# CAN2XG_TCAN.net
KiCad netlist of a schematic drawn in Altium Designer
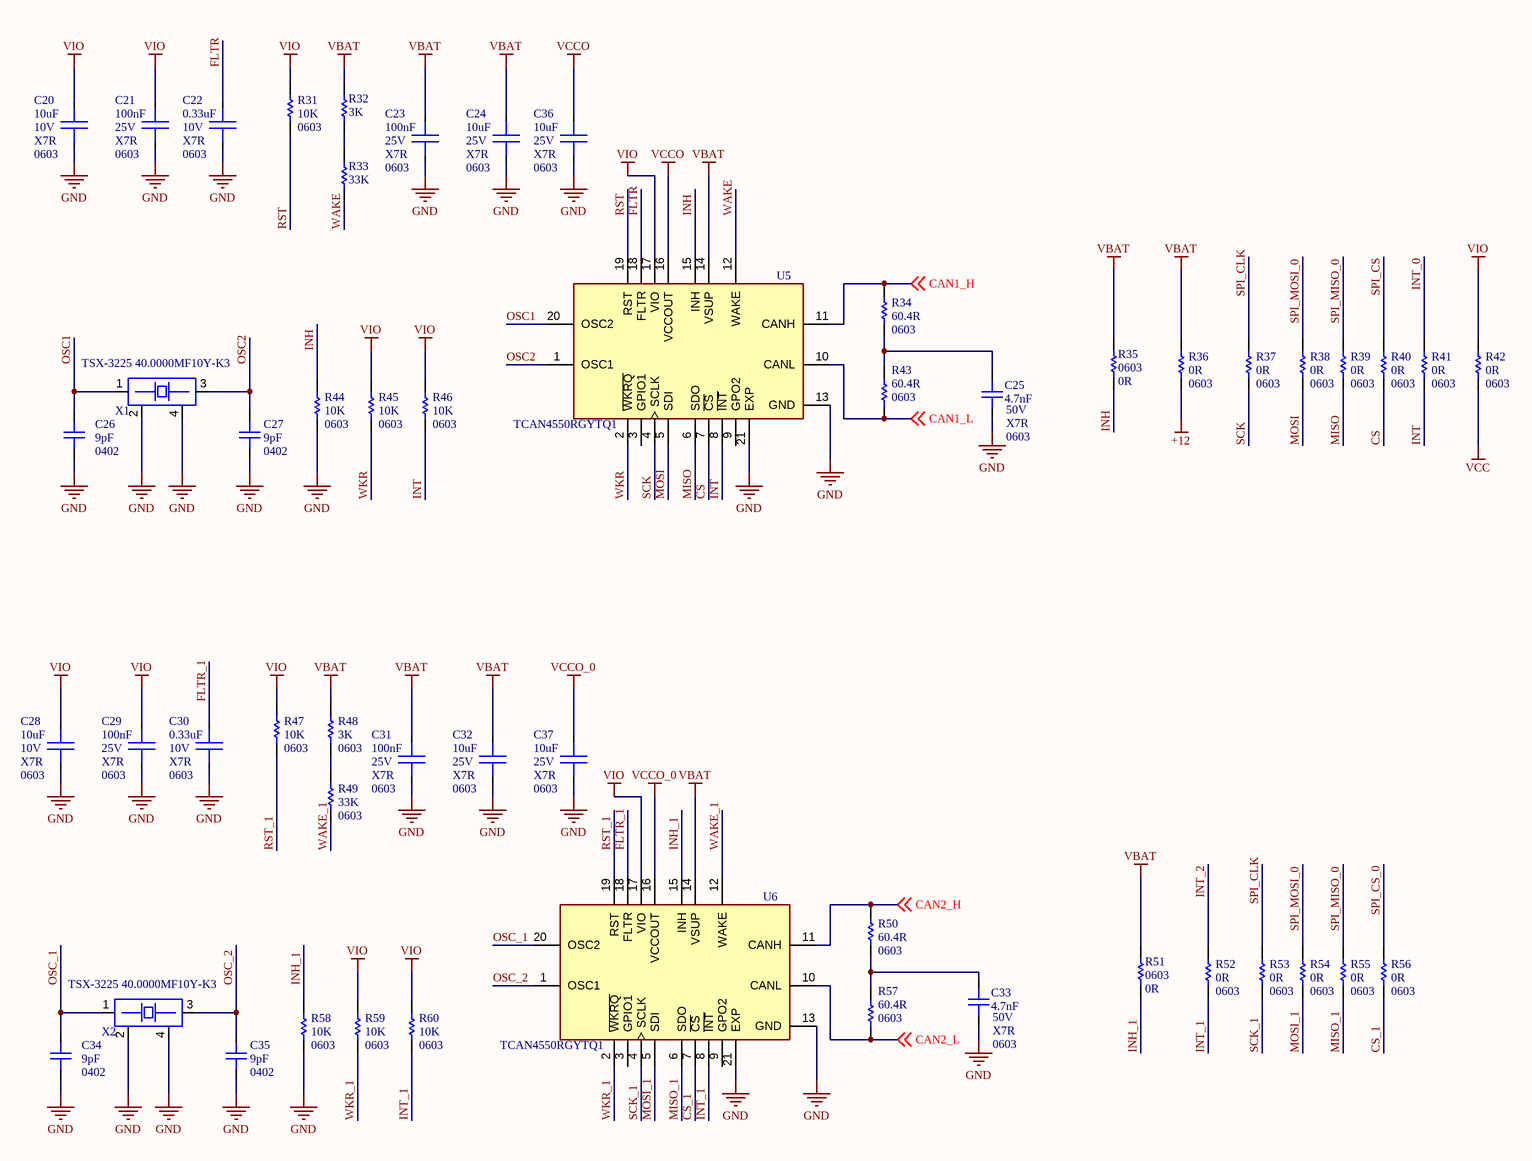
[diagram p0: CAN2XG_TCAN.SchDoc]

(export (version "E")
  (design (tool "Eeschema 10.0.6"))
  (components
    (comp (ref "C20")
      (value "10uF")
      (footprint "CAP-0603")
      (description "CAP CER 10uF 25V  0603")
      (fields
        (field (name "VOLTAGE") "10V")
        (field (name "DIELECTIRC") "X7R")
        (field (name "CASE/PACKAGE") "0603")
      )
      (libsource (lib "CAN2ET") (part "C10uF  0603"))
    )
    (comp (ref "C21")
      (value "100nF")
      (footprint "CAP-0603")
      (description "CAP CER 100nF 25V X7R 0603")
      (fields
        (field (name "VOLTAGE") "25V")
        (field (name "DIELECTIRC") "X7R")
        (field (name "CASE/PACKAGE") "0603")
      )
      (libsource (lib "CAN2ET") (part "C10uF  0603"))
    )
    (comp (ref "C22")
      (value "0.33uF")
      (footprint "CAP-0603")
      (description "CAP CER 0.33uF 10V  0603")
      (fields
        (field (name "VOLTAGE") "10V")
        (field (name "DIELECTIRC") "X7R")
        (field (name "CASE/PACKAGE") "0603")
      )
      (libsource (lib "CAN2ET") (part "C10uF  0603"))
    )
    (comp (ref "C23")
      (value "100nF")
      (footprint "CAP-0603")
      (description "CAP CER 100nF 25V X7R 0603")
      (fields
        (field (name "VOLTAGE") "25V")
        (field (name "DIELECTIRC") "X7R")
        (field (name "CASE/PACKAGE") "0603")
      )
      (libsource (lib "CAN2ET") (part "C10uF  0603"))
    )
    (comp (ref "C24")
      (value "10uF")
      (footprint "CAP-0603")
      (description "CAP CER 10uF 25V  0603")
      (fields
        (field (name "VOLTAGE") "25V")
        (field (name "DIELECTIRC") "X7R")
        (field (name "CASE/PACKAGE") "0603")
      )
      (libsource (lib "CAN2ET") (part "C10uF  0603"))
    )
    (comp (ref "C25")
      (value "4.7nF")
      (footprint "CAP-0603")
      (description "CAP CER 4.7nF 50V X7R 0603")
      (fields
        (field (name "VOLTAGE") "50V")
        (field (name "DIELECTRIC") "X7R")
        (field (name "CASE/PACKAGE") "0603")
      )
      (libsource (lib "CN2XET") (part "CS0805KRX7RYBB472"))
    )
    (comp (ref "C26")
      (value "9pF")
      (footprint "CAPC0402")
      (description "CAP CER 9PF 50V X7R 0402")
      (fields (field (name "CASE/PACKAGE") "0402") (field (name "VOLTAGE") "50V"))
      (libsource (lib "CN2XET") (part "CQ0805BRNPOYBN8R2"))
    )
    (comp (ref "C27")
      (value "9pF")
      (footprint "CAPC0402")
      (description "CAP CER 9PF 50V X7R 0402")
      (fields (field (name "CASE/PACKAGE") "0402") (field (name "VOLTAGE") "50V"))
      (libsource (lib "CN2XET") (part "CQ0805BRNPOYBN8R2"))
    )
    (comp (ref "C28")
      (value "10uF")
      (footprint "CAP-0603")
      (description "CAP CER 10uF 25V  0603")
      (fields
        (field (name "VOLTAGE") "10V")
        (field (name "DIELECTIRC") "X7R")
        (field (name "CASE/PACKAGE") "0603")
      )
      (libsource (lib "CAN2ET") (part "C10uF  0603"))
    )
    (comp (ref "C29")
      (value "100nF")
      (footprint "CAP-0603")
      (description "CAP CER 100nF 25V X7R 0603")
      (fields
        (field (name "VOLTAGE") "25V")
        (field (name "DIELECTIRC") "X7R")
        (field (name "CASE/PACKAGE") "0603")
      )
      (libsource (lib "CAN2ET") (part "C10uF  0603"))
    )
    (comp (ref "C30")
      (value "0.33uF")
      (footprint "CAP-0603")
      (description "CAP CER 0.33uF 10V  0603")
      (fields
        (field (name "VOLTAGE") "10V")
        (field (name "DIELECTIRC") "X7R")
        (field (name "CASE/PACKAGE") "0603")
      )
      (libsource (lib "CAN2ET") (part "C10uF  0603"))
    )
    (comp (ref "C31")
      (value "100nF")
      (footprint "CAP-0603")
      (description "CAP CER 100nF 25V X7R 0603")
      (fields
        (field (name "VOLTAGE") "25V")
        (field (name "DIELECTIRC") "X7R")
        (field (name "CASE/PACKAGE") "0603")
      )
      (libsource (lib "CAN2ET") (part "C10uF  0603"))
    )
    (comp (ref "C32")
      (value "10uF")
      (footprint "CAP-0603")
      (description "CAP CER 10uF 25V  0603")
      (fields
        (field (name "VOLTAGE") "25V")
        (field (name "DIELECTIRC") "X7R")
        (field (name "CASE/PACKAGE") "0603")
      )
      (libsource (lib "CAN2ET") (part "C10uF  0603"))
    )
    (comp (ref "C33")
      (value "4.7nF")
      (footprint "CAP-0603")
      (description "CAP CER 4.7nF 50V X7R 0603")
      (fields
        (field (name "VOLTAGE") "50V")
        (field (name "DIELECTRIC") "X7R")
        (field (name "CASE/PACKAGE") "0603")
      )
      (libsource (lib "CN2XET") (part "CS0805KRX7RYBB472"))
    )
    (comp (ref "C34")
      (value "9pF")
      (footprint "CAPC0402")
      (description "CAP CER 9PF 50V X7R 0402")
      (fields (field (name "CASE/PACKAGE") "0402") (field (name "VOLTAGE") "50V"))
      (libsource (lib "CN2XET") (part "CQ0805BRNPOYBN8R2"))
    )
    (comp (ref "C35")
      (value "9pF")
      (footprint "CAPC0402")
      (description "CAP CER 9PF 50V X7R 0402")
      (fields (field (name "CASE/PACKAGE") "0402") (field (name "VOLTAGE") "50V"))
      (libsource (lib "CN2XET") (part "CQ0805BRNPOYBN8R2"))
    )
    (comp (ref "C36")
      (value "10uF")
      (footprint "CAP-0603")
      (description "CAP CER 10uF 25V  0603")
      (fields
        (field (name "VOLTAGE") "25V")
        (field (name "DIELECTIRC") "X7R")
        (field (name "CASE/PACKAGE") "0603")
      )
      (libsource (lib "CAN2ET") (part "C10uF  0603"))
    )
    (comp (ref "C37")
      (value "10uF")
      (footprint "CAP-0603")
      (description "CAP CER 10uF 25V  0603")
      (fields
        (field (name "VOLTAGE") "25V")
        (field (name "DIELECTIRC") "X7R")
        (field (name "CASE/PACKAGE") "0603")
      )
      (libsource (lib "CAN2ET") (part "C10uF  0603"))
    )
    (comp (ref "R31")
      (value "10K")
      (footprint "RESC0603")
      (description "Thick Film Resistor -  10K, 1%, 0603")
      (fields (field (name "CASE/PACKAGE") "0603"))
      (libsource (lib "CN2XET") (part "ERJ6ENF1002V"))
    )
    (comp (ref "R32")
      (value "3K")
      (footprint "RESC0603")
      (description "Thick Film Resistor -  3K, 1%, 0603")
      (libsource (lib "CN2XET") (part "ERJ6ENF1002V"))
    )
    (comp (ref "R33")
      (value "33K")
      (footprint "RESC0603")
      (description "Thick Film Resistor -  33K, 1%, 0603")
      (libsource (lib "CN2XET") (part "ERJ6ENF1002V"))
    )
    (comp (ref "R34")
      (value "60.4R")
      (footprint "RESC0603")
      (description "Thick Film Resistor -  60.4R, 1%, 0603")
      (fields (field (name "CASE/PACKAGE") "0603"))
      (libsource (lib "CN2XET") (part "RC0805FR-0760R4L"))
    )
    (comp (ref "R35")
      (value "0R")
      (footprint "RESC0603")
      (description "Thick Film Resistor -  0R , 1%, 0603")
      (fields (field (name "CASE/PACKAGE") "0603"))
      (libsource (lib "CN2XET") (part "RC0805FR-0760R4L"))
    )
    (comp (ref "R36")
      (value "0R")
      (footprint "RESC0603")
      (description "Thick Film Resistor -  0R , 1%, 0603")
      (fields (field (name "CASE/PACKAGE") "0603"))
      (libsource (lib "CN2XET") (part "RC0805FR-0760R4L"))
    )
    (comp (ref "R37")
      (value "0R")
      (footprint "RESC0603")
      (description "Thick Film Resistor -  0R , 1%, 0603")
      (fields (field (name "CASE/PACKAGE") "0603"))
      (libsource (lib "CN2XET") (part "RC0805FR-0760R4L"))
    )
    (comp (ref "R38")
      (value "0R")
      (footprint "RESC0603")
      (description "Thick Film Resistor -  0R , 1%, 0603")
      (fields (field (name "CASE/PACKAGE") "0603"))
      (libsource (lib "CN2XET") (part "RC0805FR-0760R4L"))
    )
    (comp (ref "R39")
      (value "0R")
      (footprint "RESC0603")
      (description "Thick Film Resistor -  0R , 1%, 0603")
      (fields (field (name "CASE/PACKAGE") "0603"))
      (libsource (lib "CN2XET") (part "RC0805FR-0760R4L"))
    )
    (comp (ref "R40")
      (value "0R")
      (footprint "RESC0603")
      (description "Thick Film Resistor -  0R , 1%, 0603")
      (fields (field (name "CASE/PACKAGE") "0603"))
      (libsource (lib "CN2XET") (part "RC0805FR-0760R4L"))
    )
    (comp (ref "R41")
      (value "0R")
      (footprint "RESC0603")
      (description "Thick Film Resistor -  0R , 1%, 0603")
      (fields (field (name "CASE/PACKAGE") "0603"))
      (libsource (lib "CN2XET") (part "RC0805FR-0760R4L"))
    )
    (comp (ref "R42")
      (value "0R")
      (footprint "RESC0603")
      (description "Thick Film Resistor -  0R , 1%, 0603")
      (fields (field (name "CASE/PACKAGE") "0603"))
      (libsource (lib "CN2XET") (part "RC0805FR-0760R4L"))
    )
    (comp (ref "R43")
      (value "60.4R")
      (footprint "RESC0603")
      (description "Thick Film Resistor -  60.4R, 1%, 0603")
      (fields (field (name "CASE/PACKAGE") "0603"))
      (libsource (lib "CN2XET") (part "RC0805FR-0760R4L"))
    )
    (comp (ref "R44")
      (value "10K")
      (footprint "RESC0603")
      (description "Thick Film Resistor -  10K, 1%, 0603")
      (fields (field (name "CASE/PACKAGE") "0603"))
      (libsource (lib "CN2XET") (part "ERJ6ENF1002V"))
    )
    (comp (ref "R45")
      (value "10K")
      (footprint "RESC0603")
      (description "Thick Film Resistor -  10K, 1%, 0603")
      (fields (field (name "CASE/PACKAGE") "0603"))
      (libsource (lib "CN2XET") (part "ERJ6ENF1002V"))
    )
    (comp (ref "R46")
      (value "10K")
      (footprint "RESC0603")
      (description "Thick Film Resistor -  10K, 1%, 0603")
      (fields (field (name "CASE/PACKAGE") "0603"))
      (libsource (lib "CN2XET") (part "ERJ6ENF1002V"))
    )
    (comp (ref "R47")
      (value "10K")
      (footprint "RESC0603")
      (description "Thick Film Resistor -  10K, 1%, 0603")
      (fields (field (name "CASE/PACKAGE") "0603"))
      (libsource (lib "CN2XET") (part "ERJ6ENF1002V"))
    )
    (comp (ref "R48")
      (value "3K")
      (footprint "RESC0603")
      (description "Thick Film Resistor -  3K, 1%, 0603")
      (fields (field (name "CASE/PACKAGE") "0603"))
      (libsource (lib "CN2XET") (part "ERJ6ENF1002V"))
    )
    (comp (ref "R49")
      (value "33K")
      (footprint "RESC0603")
      (description "Thick Film Resistor -  33K, 1%, 0603")
      (fields (field (name "CASE/PACKAGE") "0603"))
      (libsource (lib "CN2XET") (part "ERJ6ENF1002V"))
    )
    (comp (ref "R50")
      (value "60.4R")
      (footprint "RESC0603")
      (description "Thick Film Resistor -  60.4R, 1%, 0603")
      (fields (field (name "CASE/PACKAGE") "0603"))
      (libsource (lib "CN2XET") (part "RC0805FR-0760R4L"))
    )
    (comp (ref "R51")
      (value "0R")
      (footprint "RESC0603")
      (description "Thick Film Resistor -  0R , 1%, 0603")
      (fields (field (name "CASE/PACKAGE") "0603"))
      (libsource (lib "CN2XET") (part "RC0805FR-0760R4L"))
    )
    (comp (ref "R52")
      (value "0R")
      (footprint "RESC0603")
      (description "Thick Film Resistor -  0R , 1%, 0603")
      (fields (field (name "CASE/PACKAGE") "0603"))
      (libsource (lib "CN2XET") (part "RC0805FR-0760R4L"))
    )
    (comp (ref "R53")
      (value "0R")
      (footprint "RESC0603")
      (description "Thick Film Resistor -  0R , 1%, 0603")
      (fields (field (name "CASE/PACKAGE") "0603"))
      (libsource (lib "CN2XET") (part "RC0805FR-0760R4L"))
    )
    (comp (ref "R54")
      (value "0R")
      (footprint "RESC0603")
      (description "Thick Film Resistor -  0R , 1%, 0603")
      (fields (field (name "CASE/PACKAGE") "0603"))
      (libsource (lib "CN2XET") (part "RC0805FR-0760R4L"))
    )
    (comp (ref "R55")
      (value "0R")
      (footprint "RESC0603")
      (description "Thick Film Resistor -  0R , 1%, 0603")
      (fields (field (name "CASE/PACKAGE") "0603"))
      (libsource (lib "CN2XET") (part "RC0805FR-0760R4L"))
    )
    (comp (ref "R56")
      (value "0R")
      (footprint "RESC0603")
      (description "Thick Film Resistor -  0R , 1%, 0603")
      (fields (field (name "CASE/PACKAGE") "0603"))
      (libsource (lib "CN2XET") (part "RC0805FR-0760R4L"))
    )
    (comp (ref "R57")
      (value "60.4R")
      (footprint "RESC0603")
      (description "Thick Film Resistor -  60.4R, 1%, 0603")
      (fields (field (name "CASE/PACKAGE") "0603"))
      (libsource (lib "CN2XET") (part "RC0805FR-0760R4L"))
    )
    (comp (ref "R58")
      (value "10K")
      (footprint "RESC0603")
      (description "Thick Film Resistor -  10K, 1%, 0603")
      (fields (field (name "CASE/PACKAGE") "0603"))
      (libsource (lib "CN2XET") (part "ERJ6ENF1002V"))
    )
    (comp (ref "R59")
      (value "10K")
      (footprint "RESC0603")
      (description "Thick Film Resistor -  10K, 1%, 0603")
      (fields (field (name "CASE/PACKAGE") "0603"))
      (libsource (lib "CN2XET") (part "ERJ6ENF1002V"))
    )
    (comp (ref "R60")
      (value "10K")
      (footprint "RESC0603")
      (description "Thick Film Resistor -  10K, 1%, 0603")
      (fields (field (name "CASE/PACKAGE") "0603"))
      (libsource (lib "CN2XET") (part "ERJ6ENF1002V"))
    )
    (comp (ref "U5")
      (value "~")
      (footprint "IC_TCAN4550RGYTQ1")
      (fields (field (name "MANUFACTURER PART NUMBER") "TCAN4550RGYTQ1"))
      (libsource (lib "CAN2XG") (part "TCAN4550RGYTQ1"))
    )
    (comp (ref "U6")
      (value "~")
      (footprint "IC_TCAN4550RGYTQ1")
      (fields (field (name "MANUFACTURER PART NUMBER") "TCAN4550RGYTQ1"))
      (libsource (lib "CAN2XG") (part "TCAN4550RGYTQ1"))
    )
    (comp (ref "X1")
      (value "~")
      (footprint "Crystal_3225")
      (description "CRYSTAL 40.0000MHZ 10PF SMD")
      (fields (field (name "MANUFACTURER PART NUMBER") "TSX-3225 40.0000MF10Y-K3"))
      (libsource (lib "CAN2XG") (part "CRYSTAL_1"))
    )
    (comp (ref "X2")
      (value "~")
      (footprint "Crystal_3225")
      (description "CRYSTAL 40.0000MHZ 10PF SMD")
      (fields (field (name "MANUFACTURER PART NUMBER") "TSX-3225 40.0000MF10Y-K3"))
      (libsource (lib "CAN2XG") (part "CRYSTAL_1"))
    )
  )
  (nets
    (net (code "1") (name "+12") (class "Default")
      (node (ref "R36") (pin "1") (pinfunction "1_1") (pintype "passive"))
    )
    (net (code "2") (name "/CS") (class "Default")
      (node (ref "R40") (pin "1") (pinfunction "1_1") (pintype "passive"))
      (node (ref "U5") (pin "7") (pinfunction "~{CS}_7") (pintype "passive"))
    )
    (net (code "3") (name "/CS_1") (class "Default")
      (node (ref "R56") (pin "1") (pinfunction "1_1") (pintype "passive"))
      (node (ref "U6") (pin "7") (pinfunction "~{CS}_7") (pintype "passive"))
    )
    (net (code "4") (name "/FLTR") (class "Default")
      (node (ref "C22") (pin "2") (pinfunction "2_2") (pintype "passive"))
      (node (ref "U5") (pin "18") (pinfunction "FLTR_18") (pintype "passive"))
    )
    (net (code "5") (name "/FLTR_1") (class "Default")
      (node (ref "C30") (pin "2") (pinfunction "2_2") (pintype "passive"))
      (node (ref "U6") (pin "18") (pinfunction "FLTR_18") (pintype "passive"))
    )
    (net (code "6") (name "/INH") (class "Default")
      (node (ref "R35") (pin "2") (pinfunction "2_2") (pintype "passive"))
      (node (ref "R44") (pin "2") (pinfunction "2_2") (pintype "passive"))
      (node (ref "U5") (pin "15") (pinfunction "INH_15") (pintype "passive"))
    )
    (net (code "7") (name "/INH_1") (class "Default")
      (node (ref "R51") (pin "2") (pinfunction "2_2") (pintype "passive"))
      (node (ref "R58") (pin "2") (pinfunction "2_2") (pintype "passive"))
      (node (ref "U6") (pin "15") (pinfunction "INH_15") (pintype "passive"))
    )
    (net (code "8") (name "/INT") (class "Default")
      (node (ref "R41") (pin "1") (pinfunction "1_1") (pintype "passive"))
      (node (ref "R46") (pin "1") (pinfunction "1_1") (pintype "passive"))
      (node (ref "U5") (pin "8") (pinfunction "~{INT}_8") (pintype "passive"))
    )
    (net (code "9") (name "/INT_0") (class "Default")
      (node (ref "R41") (pin "2") (pinfunction "2_2") (pintype "passive"))
    )
    (net (code "10") (name "/INT_1") (class "Default")
      (node (ref "R52") (pin "1") (pinfunction "1_1") (pintype "passive"))
      (node (ref "R60") (pin "1") (pinfunction "1_1") (pintype "passive"))
      (node (ref "U6") (pin "8") (pinfunction "~{INT}_8") (pintype "passive"))
    )
    (net (code "11") (name "/INT_2") (class "Default")
      (node (ref "R52") (pin "2") (pinfunction "2_2") (pintype "passive"))
    )
    (net (code "12") (name "/MISO") (class "Default")
      (node (ref "R39") (pin "1") (pinfunction "1_1") (pintype "passive"))
      (node (ref "U5") (pin "6") (pinfunction "SDO_6") (pintype "passive"))
    )
    (net (code "13") (name "/MISO_1") (class "Default")
      (node (ref "R55") (pin "1") (pinfunction "1_1") (pintype "passive"))
      (node (ref "U6") (pin "6") (pinfunction "SDO_6") (pintype "passive"))
    )
    (net (code "14") (name "/MOSI") (class "Default")
      (node (ref "R38") (pin "1") (pinfunction "1_1") (pintype "passive"))
      (node (ref "U5") (pin "5") (pinfunction "SDI_5") (pintype "passive"))
    )
    (net (code "15") (name "/MOSI_1") (class "Default")
      (node (ref "R54") (pin "1") (pinfunction "1_1") (pintype "passive"))
      (node (ref "U6") (pin "5") (pinfunction "SDI_5") (pintype "passive"))
    )
    (net (code "16") (name "/OSC1") (class "Default")
      (node (ref "C26") (pin "2") (pinfunction "2_2") (pintype "passive"))
      (node (ref "U5") (pin "20") (pinfunction "OSC2_20") (pintype "passive"))
      (node (ref "X1") (pin "1") (pinfunction "1_1") (pintype "passive"))
    )
    (net (code "17") (name "/OSC2") (class "Default")
      (node (ref "C27") (pin "2") (pinfunction "2_2") (pintype "passive"))
      (node (ref "U5") (pin "1") (pinfunction "OSC1_1") (pintype "passive"))
      (node (ref "X1") (pin "3") (pinfunction "3_3") (pintype "passive"))
    )
    (net (code "18") (name "/OSC_1") (class "Default")
      (node (ref "C34") (pin "2") (pinfunction "2_2") (pintype "passive"))
      (node (ref "U6") (pin "20") (pinfunction "OSC2_20") (pintype "passive"))
      (node (ref "X2") (pin "1") (pinfunction "1_1") (pintype "passive"))
    )
    (net (code "19") (name "/OSC_2") (class "Default")
      (node (ref "C35") (pin "2") (pinfunction "2_2") (pintype "passive"))
      (node (ref "U6") (pin "1") (pinfunction "OSC1_1") (pintype "passive"))
      (node (ref "X2") (pin "3") (pinfunction "3_3") (pintype "passive"))
    )
    (net (code "20") (name "/RST") (class "Default")
      (node (ref "R31") (pin "1") (pinfunction "1_1") (pintype "passive"))
      (node (ref "U5") (pin "19") (pinfunction "RST_19") (pintype "passive"))
    )
    (net (code "21") (name "/RST_1") (class "Default")
      (node (ref "R47") (pin "1") (pinfunction "1_1") (pintype "passive"))
      (node (ref "U6") (pin "19") (pinfunction "RST_19") (pintype "passive"))
    )
    (net (code "22") (name "/SCK") (class "Default")
      (node (ref "R37") (pin "1") (pinfunction "1_1") (pintype "passive"))
      (node (ref "U5") (pin "4") (pinfunction "SCLK_4") (pintype "passive"))
    )
    (net (code "23") (name "/SCK_1") (class "Default")
      (node (ref "R53") (pin "1") (pinfunction "1_1") (pintype "passive"))
      (node (ref "U6") (pin "4") (pinfunction "SCLK_4") (pintype "passive"))
    )
    (net (code "24") (name "/SPI_CLK") (class "Default")
      (node (ref "R37") (pin "2") (pinfunction "2_2") (pintype "passive"))
      (node (ref "R53") (pin "2") (pinfunction "2_2") (pintype "passive"))
    )
    (net (code "25") (name "/SPI_CS") (class "Default")
      (node (ref "R40") (pin "2") (pinfunction "2_2") (pintype "passive"))
    )
    (net (code "26") (name "/SPI_CS_0") (class "Default")
      (node (ref "R56") (pin "2") (pinfunction "2_2") (pintype "passive"))
    )
    (net (code "27") (name "/SPI_MISO_0") (class "Default")
      (node (ref "R39") (pin "2") (pinfunction "2_2") (pintype "passive"))
      (node (ref "R55") (pin "2") (pinfunction "2_2") (pintype "passive"))
    )
    (net (code "28") (name "/SPI_MOSI_0") (class "Default")
      (node (ref "R38") (pin "2") (pinfunction "2_2") (pintype "passive"))
      (node (ref "R54") (pin "2") (pinfunction "2_2") (pintype "passive"))
    )
    (net (code "29") (name "/WAKE") (class "Default")
      (node (ref "R33") (pin "1") (pinfunction "1_1") (pintype "passive"))
      (node (ref "U5") (pin "12") (pinfunction "WAKE_12") (pintype "passive"))
    )
    (net (code "30") (name "/WAKE_1") (class "Default")
      (node (ref "R49") (pin "1") (pinfunction "1_1") (pintype "passive"))
      (node (ref "U6") (pin "12") (pinfunction "WAKE_12") (pintype "passive"))
    )
    (net (code "31") (name "/WKR") (class "Default")
      (node (ref "R45") (pin "1") (pinfunction "1_1") (pintype "passive"))
      (node (ref "U5") (pin "2") (pinfunction "~{WKRQ}_2") (pintype "passive"))
    )
    (net (code "32") (name "/WKR_1") (class "Default")
      (node (ref "R59") (pin "1") (pinfunction "1_1") (pintype "passive"))
      (node (ref "U6") (pin "2") (pinfunction "~{WKRQ}_2") (pintype "passive"))
    )
    (net (code "33") (name "CAN1_H") (class "Default")
      (node (ref "R34") (pin "2") (pinfunction "2_2") (pintype "passive"))
      (node (ref "U5") (pin "11") (pinfunction "CANH_11") (pintype "passive"))
    )
    (net (code "34") (name "CAN1_L") (class "Default")
      (node (ref "R43") (pin "1") (pinfunction "1_1") (pintype "passive"))
      (node (ref "U5") (pin "10") (pinfunction "CANL_10") (pintype "passive"))
    )
    (net (code "35") (name "CAN2_H") (class "Default")
      (node (ref "R50") (pin "2") (pinfunction "2_2") (pintype "passive"))
      (node (ref "U6") (pin "11") (pinfunction "CANH_11") (pintype "passive"))
    )
    (net (code "36") (name "CAN2_L") (class "Default")
      (node (ref "R57") (pin "1") (pinfunction "1_1") (pintype "passive"))
      (node (ref "U6") (pin "10") (pinfunction "CANL_10") (pintype "passive"))
    )
    (net (code "37") (name "GND") (class "Default")
      (node (ref "C20") (pin "1") (pinfunction "1_1") (pintype "passive"))
      (node (ref "C21") (pin "1") (pinfunction "1_1") (pintype "passive"))
      (node (ref "C22") (pin "1") (pinfunction "1_1") (pintype "passive"))
      (node (ref "C23") (pin "1") (pinfunction "1_1") (pintype "passive"))
      (node (ref "C24") (pin "1") (pinfunction "1_1") (pintype "passive"))
      (node (ref "C25") (pin "1") (pinfunction "1_1") (pintype "passive"))
      (node (ref "C26") (pin "1") (pinfunction "1_1") (pintype "passive"))
      (node (ref "C27") (pin "1") (pinfunction "1_1") (pintype "passive"))
      (node (ref "C28") (pin "1") (pinfunction "1_1") (pintype "passive"))
      (node (ref "C29") (pin "1") (pinfunction "1_1") (pintype "passive"))
      (node (ref "C30") (pin "1") (pinfunction "1_1") (pintype "passive"))
      (node (ref "C31") (pin "1") (pinfunction "1_1") (pintype "passive"))
      (node (ref "C32") (pin "1") (pinfunction "1_1") (pintype "passive"))
      (node (ref "C33") (pin "1") (pinfunction "1_1") (pintype "passive"))
      (node (ref "C34") (pin "1") (pinfunction "1_1") (pintype "passive"))
      (node (ref "C35") (pin "1") (pinfunction "1_1") (pintype "passive"))
      (node (ref "C36") (pin "1") (pinfunction "1_1") (pintype "passive"))
      (node (ref "C37") (pin "1") (pinfunction "1_1") (pintype "passive"))
      (node (ref "R44") (pin "1") (pinfunction "1_1") (pintype "passive"))
      (node (ref "R58") (pin "1") (pinfunction "1_1") (pintype "passive"))
      (node (ref "U5") (pin "13") (pinfunction "GND_13") (pintype "passive"))
      (node (ref "U5") (pin "21") (pinfunction "EXP_21") (pintype "passive"))
      (node (ref "U6") (pin "13") (pinfunction "GND_13") (pintype "passive"))
      (node (ref "U6") (pin "21") (pinfunction "EXP_21") (pintype "passive"))
      (node (ref "X1") (pin "2") (pinfunction "2_2") (pintype "passive"))
      (node (ref "X1") (pin "4") (pinfunction "4_4") (pintype "passive"))
      (node (ref "X2") (pin "2") (pinfunction "2_2") (pintype "passive"))
      (node (ref "X2") (pin "4") (pinfunction "4_4") (pintype "passive"))
    )
    (net (code "38") (name "Net-(C25-Pad2)") (class "Default")
      (node (ref "C25") (pin "2") (pinfunction "2_2") (pintype "passive"))
      (node (ref "R34") (pin "1") (pinfunction "1_1") (pintype "passive"))
      (node (ref "R43") (pin "2") (pinfunction "2_2") (pintype "passive"))
    )
    (net (code "39") (name "Net-(C33-Pad2)") (class "Default")
      (node (ref "C33") (pin "2") (pinfunction "2_2") (pintype "passive"))
      (node (ref "R50") (pin "1") (pinfunction "1_1") (pintype "passive"))
      (node (ref "R57") (pin "2") (pinfunction "2_2") (pintype "passive"))
    )
    (net (code "40") (name "Net-(R32-Pad1)") (class "Default")
      (node (ref "R32") (pin "1") (pinfunction "1_1") (pintype "passive"))
      (node (ref "R33") (pin "2") (pinfunction "2_2") (pintype "passive"))
    )
    (net (code "41") (name "Net-(R48-Pad1)") (class "Default")
      (node (ref "R48") (pin "1") (pinfunction "1_1") (pintype "passive"))
      (node (ref "R49") (pin "2") (pinfunction "2_2") (pintype "passive"))
    )
    (net (code "42") (name "VBAT") (class "Default")
      (node (ref "C23") (pin "2") (pinfunction "2_2") (pintype "passive"))
      (node (ref "C24") (pin "2") (pinfunction "2_2") (pintype "passive"))
      (node (ref "C31") (pin "2") (pinfunction "2_2") (pintype "passive"))
      (node (ref "C32") (pin "2") (pinfunction "2_2") (pintype "passive"))
      (node (ref "R32") (pin "2") (pinfunction "2_2") (pintype "passive"))
      (node (ref "R35") (pin "1") (pinfunction "1_1") (pintype "passive"))
      (node (ref "R36") (pin "2") (pinfunction "2_2") (pintype "passive"))
      (node (ref "R48") (pin "2") (pinfunction "2_2") (pintype "passive"))
      (node (ref "R51") (pin "1") (pinfunction "1_1") (pintype "passive"))
      (node (ref "U5") (pin "14") (pinfunction "VSUP_14") (pintype "passive"))
      (node (ref "U6") (pin "14") (pinfunction "VSUP_14") (pintype "passive"))
    )
    (net (code "43") (name "VCC") (class "Default")
      (node (ref "R42") (pin "1") (pinfunction "1_1") (pintype "passive"))
    )
    (net (code "44") (name "VCCO") (class "Default")
      (node (ref "C36") (pin "2") (pinfunction "2_2") (pintype "passive"))
      (node (ref "U5") (pin "16") (pinfunction "VCCOUT_16") (pintype "passive"))
    )
    (net (code "45") (name "VCCO_0") (class "Default")
      (node (ref "C37") (pin "2") (pinfunction "2_2") (pintype "passive"))
      (node (ref "U6") (pin "16") (pinfunction "VCCOUT_16") (pintype "passive"))
    )
    (net (code "46") (name "VIO") (class "Default")
      (node (ref "C20") (pin "2") (pinfunction "2_2") (pintype "passive"))
      (node (ref "C21") (pin "2") (pinfunction "2_2") (pintype "passive"))
      (node (ref "C28") (pin "2") (pinfunction "2_2") (pintype "passive"))
      (node (ref "C29") (pin "2") (pinfunction "2_2") (pintype "passive"))
      (node (ref "R31") (pin "2") (pinfunction "2_2") (pintype "passive"))
      (node (ref "R42") (pin "2") (pinfunction "2_2") (pintype "passive"))
      (node (ref "R45") (pin "2") (pinfunction "2_2") (pintype "passive"))
      (node (ref "R46") (pin "2") (pinfunction "2_2") (pintype "passive"))
      (node (ref "R47") (pin "2") (pinfunction "2_2") (pintype "passive"))
      (node (ref "R59") (pin "2") (pinfunction "2_2") (pintype "passive"))
      (node (ref "R60") (pin "2") (pinfunction "2_2") (pintype "passive"))
      (node (ref "U5") (pin "17") (pinfunction "VIO_17") (pintype "passive"))
      (node (ref "U6") (pin "17") (pinfunction "VIO_17") (pintype "passive"))
    )
    (net (code "47") (name "unconnected-(U5-GPIO1-Pad3)") (class "Default")
      (node (ref "U5") (pin "3") (pinfunction "GPIO1_3") (pintype "passive"))
    )
    (net (code "48") (name "unconnected-(U5-GPO2-Pad9)") (class "Default")
      (node (ref "U5") (pin "9") (pinfunction "GPO2_9") (pintype "passive"))
    )
    (net (code "49") (name "unconnected-(U6-GPIO1-Pad3)") (class "Default")
      (node (ref "U6") (pin "3") (pinfunction "GPIO1_3") (pintype "passive"))
    )
    (net (code "50") (name "unconnected-(U6-GPO2-Pad9)") (class "Default")
      (node (ref "U6") (pin "9") (pinfunction "GPO2_9") (pintype "passive"))
    )
  )
)
